# Sheet2.net
KiCad netlist of a schematic drawn in Altium Designer
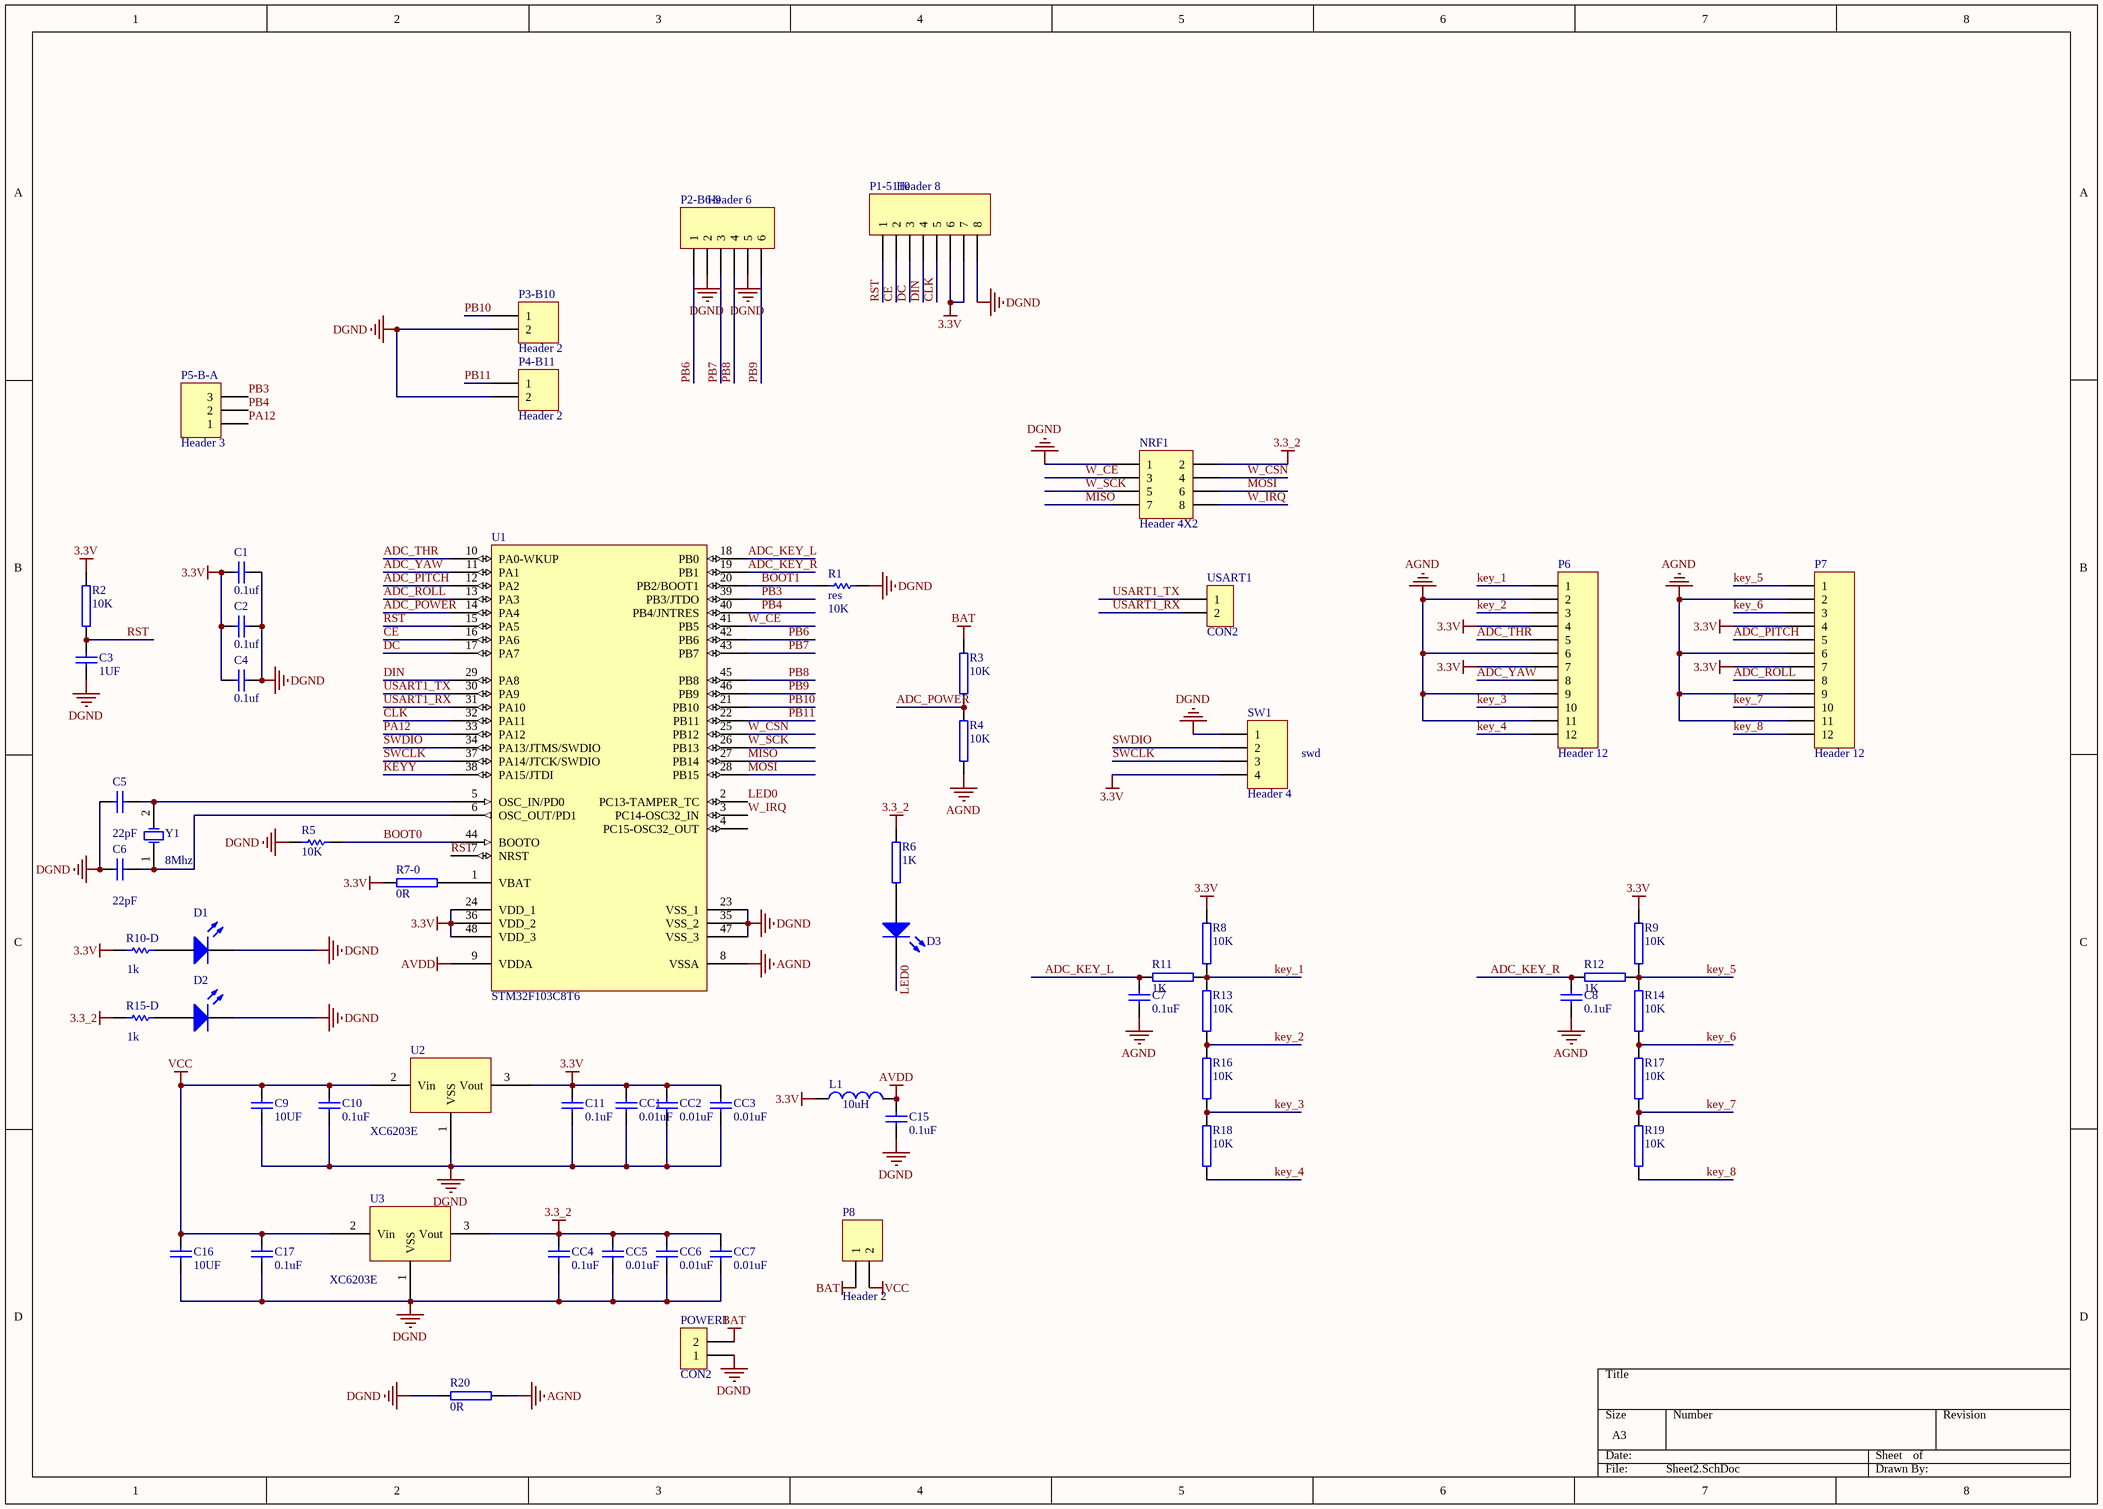
[diagram p0: Sheet2.SchDoc]

(export (version "E")
  (design (tool "Eeschema 10.0.6"))
  (components
    (comp (ref "C1")
      (value "0.1uf")
      (footprint "0603c")
      (fields (field (name "Comment") "cap"))
      (libsource (lib "bai") (part "cap"))
    )
    (comp (ref "C2")
      (value "0.1uf")
      (footprint "0603c")
      (fields (field (name "Comment") "cap"))
      (libsource (lib "bai") (part "cap"))
    )
    (comp (ref "C3")
      (value "1UF")
      (footprint "0603c")
      (fields (field (name "Comment") "cap"))
      (libsource (lib "bai") (part "cap"))
    )
    (comp (ref "C4")
      (value "0.1uf")
      (footprint "0603c")
      (fields (field (name "Comment") "cap"))
      (libsource (lib "bai") (part "cap"))
    )
    (comp (ref "C5")
      (value "22pF")
      (footprint "0603c")
      (fields (field (name "Comment") "cap"))
      (libsource (lib "bai") (part "cap"))
    )
    (comp (ref "C6")
      (value "22pF")
      (footprint "0603c")
      (fields (field (name "Comment") "cap"))
      (libsource (lib "bai") (part "cap"))
    )
    (comp (ref "C7")
      (value "0.1uF")
      (footprint "0603c")
      (fields (field (name "Comment") "cap"))
      (libsource (lib "bai") (part "cap"))
    )
    (comp (ref "C8")
      (value "0.1uF")
      (footprint "0603c")
      (fields (field (name "Comment") "cap"))
      (libsource (lib "bai") (part "cap"))
    )
    (comp (ref "C9")
      (value "10UF")
      (footprint "0805")
      (fields (field (name "Comment") "cap"))
      (libsource (lib "bai") (part "cap"))
    )
    (comp (ref "C10")
      (value "0.1uF")
      (footprint "0603c")
      (fields (field (name "Comment") "cap"))
      (libsource (lib "bai") (part "cap"))
    )
    (comp (ref "C11")
      (value "0.1uF")
      (footprint "0603c")
      (fields (field (name "Comment") "cap"))
      (libsource (lib "bai") (part "cap"))
    )
    (comp (ref "C15")
      (value "0.1uF")
      (footprint "0603c")
      (fields (field (name "Comment") "cap"))
      (libsource (lib "bai") (part "cap"))
    )
    (comp (ref "C16")
      (value "10UF")
      (footprint "0805")
      (fields (field (name "Comment") "cap"))
      (libsource (lib "bai") (part "cap"))
    )
    (comp (ref "C17")
      (value "0.1uF")
      (footprint "0603c")
      (fields (field (name "Comment") "cap"))
      (libsource (lib "bai") (part "cap"))
    )
    (comp (ref "CC1")
      (value "0.01uF")
      (footprint "0603c")
      (fields (field (name "Comment") "cap"))
      (libsource (lib "bai") (part "cap"))
    )
    (comp (ref "CC2")
      (value "0.01uF")
      (footprint "0603c")
      (fields (field (name "Comment") "cap"))
      (libsource (lib "bai") (part "cap"))
    )
    (comp (ref "CC3")
      (value "0.01uF")
      (footprint "0603c")
      (fields (field (name "Comment") "cap"))
      (libsource (lib "bai") (part "cap"))
    )
    (comp (ref "CC4")
      (value "0.1uF")
      (footprint "0603c")
      (fields (field (name "Comment") "cap"))
      (libsource (lib "bai") (part "cap"))
    )
    (comp (ref "CC5")
      (value "0.01uF")
      (footprint "0603c")
      (fields (field (name "Comment") "cap"))
      (libsource (lib "bai") (part "cap"))
    )
    (comp (ref "CC6")
      (value "0.01uF")
      (footprint "0603c")
      (fields (field (name "Comment") "cap"))
      (libsource (lib "bai") (part "cap"))
    )
    (comp (ref "CC7")
      (value "0.01uF")
      (footprint "0603c")
      (fields (field (name "Comment") "cap"))
      (libsource (lib "bai") (part "cap"))
    )
    (comp (ref "D1")
      (value "LED0")
      (footprint "0805")
      (description "Typical INFRARED GaAs LED")
      (fields (field (name "PUBLISHER") "Altium Limited"))
      (libsource (lib "Miscellaneous Devices") (part "LED0"))
    )
    (comp (ref "D2")
      (value "LED0")
      (footprint "0805")
      (description "Typical INFRARED GaAs LED")
      (fields (field (name "PUBLISHER") "Altium Limited"))
      (libsource (lib "Miscellaneous Devices") (part "LED0"))
    )
    (comp (ref "D3")
      (value "LED0")
      (footprint "0805")
      (description "Typical INFRARED GaAs LED")
      (fields (field (name "PUBLISHER") "Altium Limited"))
      (libsource (lib "Miscellaneous Devices") (part "LED0"))
    )
    (comp (ref "L1")
      (value "10uH")
      (footprint "0805")
      (fields (field (name "Comment") "Inductor"))
      (libsource (lib "bai") (part "Inductor"))
    )
    (comp (ref "NRF1")
      (value "Header 4X2")
      (footprint "HDR2X4")
      (description "Header, 4-Pin, Dual row")
      (fields (field (name "PUBLISHER") "Altium Limited"))
      (libsource (lib "Miscellaneous Connectors") (part "Header 4X2"))
    )
    (comp (ref "P1-5110")
      (value "Header 8")
      (footprint "HDR1X8")
      (description "Header, 8-Pin")
      (fields (field (name "PUBLISHER") "Altium Limited"))
      (libsource (lib "Miscellaneous Connectors") (part "Header 8"))
    )
    (comp (ref "P2-B6-9")
      (value "Header 6")
      (footprint "6p")
      (description "Header, 6-Pin")
      (fields (field (name "PUBLISHER") "Altium Limited"))
      (libsource (lib "Miscellaneous Connectors") (part "Header 6"))
    )
    (comp (ref "P3-B10")
      (value "Header 2")
      (footprint "2p")
      (description "Header, 2-Pin")
      (fields (field (name "PUBLISHER") "Altium Limited"))
      (libsource (lib "Miscellaneous Connectors") (part "Header 2"))
    )
    (comp (ref "P4-B11")
      (value "Header 2")
      (footprint "2p")
      (description "Header, 2-Pin")
      (fields (field (name "PUBLISHER") "Altium Limited"))
      (libsource (lib "Miscellaneous Connectors") (part "Header 2"))
    )
    (comp (ref "P5-B-A")
      (value "Header 3")
      (footprint "HDR1X3")
      (description "Header, 3-Pin")
      (fields (field (name "PUBLISHER") "Altium Limited"))
      (libsource (lib "Miscellaneous Connectors") (part "Header 3"))
    )
    (comp (ref "P6")
      (value "Header 12")
      (footprint "12p")
      (description "Header, 12-Pin")
      (fields (field (name "PUBLISHER") "Altium Limited"))
      (libsource (lib "Miscellaneous Connectors") (part "Header 12"))
    )
    (comp (ref "P7")
      (value "Header 12")
      (footprint "12p")
      (description "Header, 12-Pin")
      (fields (field (name "PUBLISHER") "Altium Limited"))
      (libsource (lib "Miscellaneous Connectors") (part "Header 12"))
    )
    (comp (ref "P8")
      (value "Header 2")
      (footprint "2p")
      (description "Header, 2-Pin")
      (fields (field (name "PUBLISHER") "Altium Limited"))
      (libsource (lib "") (part "Header 2_1"))
    )
    (comp (ref "POWER1") (value "CON2") (footprint "2p") (libsource (lib "") (part "CON2_1")))
    (comp (ref "R1")
      (value "res")
      (footprint "0603c")
      (fields (field (name "RES") "10K"))
      (libsource (lib "bai") (part "res"))
    )
    (comp (ref "R2") (value "10K") (footprint "0603c") (libsource (lib "常用元件库") (part "RES")))
    (comp (ref "R3") (value "10K") (footprint "0603c") (libsource (lib "常用元件库") (part "RES")))
    (comp (ref "R4") (value "10K") (footprint "0603c") (libsource (lib "常用元件库") (part "RES")))
    (comp (ref "R5")
      (value "res")
      (footprint "0603c")
      (fields (field (name "RES") "10K"))
      (libsource (lib "bai") (part "res"))
    )
    (comp (ref "R6") (value "1K") (footprint "0603c") (libsource (lib "常用元件库") (part "RES")))
    (comp (ref "R7-0") (value "0R") (footprint "0805") (libsource (lib "常用元件库") (part "RES")))
    (comp (ref "R8") (value "10K") (footprint "0603c") (libsource (lib "常用元件库") (part "RES")))
    (comp (ref "R9") (value "10K") (footprint "0603c") (libsource (lib "常用元件库") (part "RES")))
    (comp (ref "R10-D")
      (value "res")
      (footprint "0603c")
      (fields (field (name "RES") "1k"))
      (libsource (lib "bai") (part "res"))
    )
    (comp (ref "R11") (value "1K") (footprint "0603c") (libsource (lib "常用元件库") (part "RES")))
    (comp (ref "R12") (value "1K") (footprint "0603c") (libsource (lib "常用元件库") (part "RES")))
    (comp (ref "R13") (value "10K") (footprint "0603c") (libsource (lib "常用元件库") (part "RES")))
    (comp (ref "R14") (value "10K") (footprint "0603c") (libsource (lib "常用元件库") (part "RES")))
    (comp (ref "R15-D")
      (value "res")
      (footprint "0603c")
      (fields (field (name "RES") "1k"))
      (libsource (lib "bai") (part "res"))
    )
    (comp (ref "R16") (value "10K") (footprint "0603c") (libsource (lib "常用元件库") (part "RES")))
    (comp (ref "R17") (value "10K") (footprint "0603c") (libsource (lib "常用元件库") (part "RES")))
    (comp (ref "R18") (value "10K") (footprint "0603c") (libsource (lib "常用元件库") (part "RES")))
    (comp (ref "R19") (value "10K") (footprint "0603c") (libsource (lib "常用元件库") (part "RES")))
    (comp (ref "R20") (value "0R") (footprint "0805") (libsource (lib "常用元件库") (part "RES")))
    (comp (ref "SW1")
      (value "Header 4")
      (footprint "HDR1X4")
      (description "Header, 4-Pin")
      (fields (field (name "PUBLISHER") "Altium Limited"))
      (libsource (lib "Miscellaneous Connectors") (part "Header 4"))
    )
    (comp (ref "U1")
      (value "STM32F103C8T6")
      (footprint "LQFP48S")
      (libsource (lib "bai") (part "STM32F103C8T6"))
    )
    (comp (ref "U2") (value "XC6203E") (footprint "SOT-89") (libsource (lib "文哥做的") (part "XC6203")))
    (comp (ref "U3") (value "XC6203E") (footprint "SOT-89") (libsource (lib "文哥做的") (part "XC6203")))
    (comp (ref "USART1") (value "CON2") (footprint "SIP2") (libsource (lib "常用元件库") (part "CON2")))
    (comp (ref "Y1")
      (value "5032xtal")
      (footprint "晶振")
      (fields (field (name "ALTIUM_UNNAMED_1") "8Mhz"))
      (libsource (lib "bai") (part "5032xtal"))
    )
  )
  (nets
    (net (code "1") (name "/ADC_KEY_L") (class "Default")
      (node (ref "C7") (pin "2") (pinfunction "2_2") (pintype "passive"))
      (node (ref "R11") (pin "2") (pinfunction "2_2") (pintype "passive"))
      (node (ref "U1") (pin "18") (pinfunction "PB0_18") (pintype "bidirectional"))
    )
    (net (code "2") (name "/ADC_KEY_R") (class "Default")
      (node (ref "C8") (pin "2") (pinfunction "2_2") (pintype "passive"))
      (node (ref "R12") (pin "2") (pinfunction "2_2") (pintype "passive"))
      (node (ref "U1") (pin "19") (pinfunction "PB1_19") (pintype "bidirectional"))
    )
    (net (code "3") (name "/ADC_PITCH") (class "Default")
      (node (ref "P7") (pin "5") (pinfunction "5_5") (pintype "passive"))
      (node (ref "U1") (pin "12") (pinfunction "PA2_12") (pintype "bidirectional"))
    )
    (net (code "4") (name "/ADC_POWER") (class "Default")
      (node (ref "R3") (pin "1") (pinfunction "1_1") (pintype "passive"))
      (node (ref "R4") (pin "2") (pinfunction "2_2") (pintype "passive"))
      (node (ref "U1") (pin "14") (pinfunction "PA4_14") (pintype "bidirectional"))
    )
    (net (code "5") (name "/ADC_ROLL") (class "Default")
      (node (ref "P7") (pin "8") (pinfunction "8_8") (pintype "passive"))
      (node (ref "U1") (pin "13") (pinfunction "PA3_13") (pintype "bidirectional"))
    )
    (net (code "6") (name "/ADC_THR") (class "Default")
      (node (ref "P6") (pin "5") (pinfunction "5_5") (pintype "passive"))
      (node (ref "U1") (pin "10") (pinfunction "PA0-WKUP_10") (pintype "bidirectional"))
    )
    (net (code "7") (name "/ADC_YAW") (class "Default")
      (node (ref "P6") (pin "8") (pinfunction "8_8") (pintype "passive"))
      (node (ref "U1") (pin "11") (pinfunction "PA1_11") (pintype "bidirectional"))
    )
    (net (code "8") (name "/BOOT0") (class "Default")
      (node (ref "R5") (pin "2") (pinfunction "2_2") (pintype "passive"))
      (node (ref "U1") (pin "44") (pinfunction "BOOTO_44") (pintype "input"))
    )
    (net (code "9") (name "/BOOT1") (class "Default")
      (node (ref "R1") (pin "1") (pinfunction "1_1") (pintype "passive"))
      (node (ref "U1") (pin "20") (pinfunction "PB2/BOOT1_20") (pintype "bidirectional"))
    )
    (net (code "10") (name "/CE") (class "Default")
      (node (ref "P1-5110") (pin "2") (pinfunction "2_2") (pintype "passive"))
      (node (ref "U1") (pin "16") (pinfunction "PA6_16") (pintype "bidirectional"))
    )
    (net (code "11") (name "/CLK") (class "Default")
      (node (ref "P1-5110") (pin "5") (pinfunction "5_5") (pintype "passive"))
      (node (ref "U1") (pin "32") (pinfunction "PA11_32") (pintype "bidirectional"))
    )
    (net (code "12") (name "/DC") (class "Default")
      (node (ref "P1-5110") (pin "3") (pinfunction "3_3") (pintype "passive"))
      (node (ref "U1") (pin "17") (pinfunction "PA7_17") (pintype "bidirectional"))
    )
    (net (code "13") (name "/DIN") (class "Default")
      (node (ref "P1-5110") (pin "4") (pinfunction "4_4") (pintype "passive"))
      (node (ref "U1") (pin "29") (pinfunction "PA8_29") (pintype "bidirectional"))
    )
    (net (code "14") (name "/KEYY") (class "Default")
      (node (ref "U1") (pin "38") (pinfunction "PA15/JTDI_38") (pintype "bidirectional"))
    )
    (net (code "15") (name "/LED0") (class "Default")
      (node (ref "D3") (pin "2") (pinfunction "K_2") (pintype "passive"))
      (node (ref "U1") (pin "2") (pinfunction "PC13-TAMPER_TC_2") (pintype "bidirectional"))
    )
    (net (code "16") (name "/MISO") (class "Default")
      (node (ref "NRF1") (pin "7") (pinfunction "7_7") (pintype "passive"))
      (node (ref "U1") (pin "27") (pinfunction "PB14_27") (pintype "bidirectional"))
    )
    (net (code "17") (name "/MOSI") (class "Default")
      (node (ref "NRF1") (pin "6") (pinfunction "6_6") (pintype "passive"))
      (node (ref "U1") (pin "28") (pinfunction "PB15_28") (pintype "bidirectional"))
    )
    (net (code "18") (name "/PA12") (class "Default")
      (node (ref "P5-B-A") (pin "1") (pinfunction "1_1") (pintype "passive"))
      (node (ref "U1") (pin "33") (pinfunction "PA12_33") (pintype "bidirectional"))
    )
    (net (code "19") (name "/PB3") (class "Default")
      (node (ref "P5-B-A") (pin "3") (pinfunction "3_3") (pintype "passive"))
      (node (ref "U1") (pin "39") (pinfunction "PB3/JTDO_39") (pintype "bidirectional"))
    )
    (net (code "20") (name "/PB4") (class "Default")
      (node (ref "P5-B-A") (pin "2") (pinfunction "2_2") (pintype "passive"))
      (node (ref "U1") (pin "40") (pinfunction "PB4/JNTRES_40") (pintype "bidirectional"))
    )
    (net (code "21") (name "/PB6") (class "Default")
      (node (ref "P2-B6-9") (pin "1") (pinfunction "1_1") (pintype "passive"))
      (node (ref "U1") (pin "42") (pinfunction "PB6_42") (pintype "bidirectional"))
    )
    (net (code "22") (name "/PB7") (class "Default")
      (node (ref "P2-B6-9") (pin "3") (pinfunction "3_3") (pintype "passive"))
      (node (ref "U1") (pin "43") (pinfunction "PB7_43") (pintype "bidirectional"))
    )
    (net (code "23") (name "/PB8") (class "Default")
      (node (ref "P2-B6-9") (pin "4") (pinfunction "4_4") (pintype "passive"))
      (node (ref "U1") (pin "45") (pinfunction "PB8_45") (pintype "bidirectional"))
    )
    (net (code "24") (name "/PB9") (class "Default")
      (node (ref "P2-B6-9") (pin "6") (pinfunction "6_6") (pintype "passive"))
      (node (ref "U1") (pin "46") (pinfunction "PB9_46") (pintype "bidirectional"))
    )
    (net (code "25") (name "/PB10") (class "Default")
      (node (ref "P3-B10") (pin "1") (pinfunction "1_1") (pintype "passive"))
      (node (ref "U1") (pin "21") (pinfunction "PB10_21") (pintype "bidirectional"))
    )
    (net (code "26") (name "/PB11") (class "Default")
      (node (ref "P4-B11") (pin "1") (pinfunction "1_1") (pintype "passive"))
      (node (ref "U1") (pin "22") (pinfunction "PB11_22") (pintype "bidirectional"))
    )
    (net (code "27") (name "/RST") (class "Default")
      (node (ref "C3") (pin "2") (pinfunction "2_2") (pintype "passive"))
      (node (ref "P1-5110") (pin "1") (pinfunction "1_1") (pintype "passive"))
      (node (ref "R2") (pin "1") (pinfunction "1_1") (pintype "passive"))
      (node (ref "U1") (pin "15") (pinfunction "PA5_15") (pintype "bidirectional"))
      (node (ref "U1") (pin "7") (pinfunction "NRST_7") (pintype "bidirectional"))
    )
    (net (code "28") (name "/SWCLK") (class "Default")
      (node (ref "SW1") (pin "3") (pinfunction "3_3") (pintype "passive"))
      (node (ref "U1") (pin "37") (pinfunction "PA14/JTCK/SWDIO_37") (pintype "bidirectional"))
    )
    (net (code "29") (name "/SWDIO") (class "Default")
      (node (ref "SW1") (pin "2") (pinfunction "2_2") (pintype "passive"))
      (node (ref "U1") (pin "34") (pinfunction "PA13/JTMS/SWDIO_34") (pintype "bidirectional"))
    )
    (net (code "30") (name "/USART1_RX") (class "Default")
      (node (ref "U1") (pin "31") (pinfunction "PA10_31") (pintype "bidirectional"))
      (node (ref "USART1") (pin "2") (pinfunction "2_2") (pintype "passive"))
    )
    (net (code "31") (name "/USART1_TX") (class "Default")
      (node (ref "U1") (pin "30") (pinfunction "PA9_30") (pintype "bidirectional"))
      (node (ref "USART1") (pin "1") (pinfunction "1_1") (pintype "passive"))
    )
    (net (code "32") (name "/W_CE") (class "Default")
      (node (ref "NRF1") (pin "3") (pinfunction "3_3") (pintype "passive"))
      (node (ref "U1") (pin "41") (pinfunction "PB5_41") (pintype "bidirectional"))
    )
    (net (code "33") (name "/W_CSN") (class "Default")
      (node (ref "NRF1") (pin "4") (pinfunction "4_4") (pintype "passive"))
      (node (ref "U1") (pin "25") (pinfunction "PB12_25") (pintype "bidirectional"))
    )
    (net (code "34") (name "/W_IRQ") (class "Default")
      (node (ref "NRF1") (pin "8") (pinfunction "8_8") (pintype "passive"))
      (node (ref "U1") (pin "3") (pinfunction "PC14-OSC32_IN_3") (pintype "bidirectional"))
    )
    (net (code "35") (name "/W_SCK") (class "Default")
      (node (ref "NRF1") (pin "5") (pinfunction "5_5") (pintype "passive"))
      (node (ref "U1") (pin "26") (pinfunction "PB13_26") (pintype "bidirectional"))
    )
    (net (code "36") (name "/key_1") (class "Default")
      (node (ref "P6") (pin "1") (pinfunction "1_1") (pintype "passive"))
      (node (ref "R11") (pin "1") (pinfunction "1_1") (pintype "passive"))
      (node (ref "R13") (pin "2") (pinfunction "2_2") (pintype "passive"))
      (node (ref "R8") (pin "1") (pinfunction "1_1") (pintype "passive"))
    )
    (net (code "37") (name "/key_2") (class "Default")
      (node (ref "P6") (pin "3") (pinfunction "3_3") (pintype "passive"))
      (node (ref "R13") (pin "1") (pinfunction "1_1") (pintype "passive"))
      (node (ref "R16") (pin "2") (pinfunction "2_2") (pintype "passive"))
    )
    (net (code "38") (name "/key_3") (class "Default")
      (node (ref "P6") (pin "10") (pinfunction "10_10") (pintype "passive"))
      (node (ref "R16") (pin "1") (pinfunction "1_1") (pintype "passive"))
      (node (ref "R18") (pin "2") (pinfunction "2_2") (pintype "passive"))
    )
    (net (code "39") (name "/key_4") (class "Default")
      (node (ref "P6") (pin "12") (pinfunction "12_12") (pintype "passive"))
      (node (ref "R18") (pin "1") (pinfunction "1_1") (pintype "passive"))
    )
    (net (code "40") (name "/key_5") (class "Default")
      (node (ref "P7") (pin "1") (pinfunction "1_1") (pintype "passive"))
      (node (ref "R12") (pin "1") (pinfunction "1_1") (pintype "passive"))
      (node (ref "R14") (pin "2") (pinfunction "2_2") (pintype "passive"))
      (node (ref "R9") (pin "1") (pinfunction "1_1") (pintype "passive"))
    )
    (net (code "41") (name "/key_6") (class "Default")
      (node (ref "P7") (pin "3") (pinfunction "3_3") (pintype "passive"))
      (node (ref "R14") (pin "1") (pinfunction "1_1") (pintype "passive"))
      (node (ref "R17") (pin "2") (pinfunction "2_2") (pintype "passive"))
    )
    (net (code "42") (name "/key_7") (class "Default")
      (node (ref "P7") (pin "10") (pinfunction "10_10") (pintype "passive"))
      (node (ref "R17") (pin "1") (pinfunction "1_1") (pintype "passive"))
      (node (ref "R19") (pin "2") (pinfunction "2_2") (pintype "passive"))
    )
    (net (code "43") (name "/key_8") (class "Default")
      (node (ref "P7") (pin "12") (pinfunction "12_12") (pintype "passive"))
      (node (ref "R19") (pin "1") (pinfunction "1_1") (pintype "passive"))
    )
    (net (code "44") (name "3.3V") (class "Default")
      (node (ref "C1") (pin "2") (pinfunction "2_2") (pintype "passive"))
      (node (ref "C11") (pin "2") (pinfunction "2_2") (pintype "passive"))
      (node (ref "C2") (pin "2") (pinfunction "2_2") (pintype "passive"))
      (node (ref "C4") (pin "2") (pinfunction "2_2") (pintype "passive"))
      (node (ref "CC1") (pin "2") (pinfunction "2_2") (pintype "passive"))
      (node (ref "CC2") (pin "2") (pinfunction "2_2") (pintype "passive"))
      (node (ref "CC3") (pin "2") (pinfunction "2_2") (pintype "passive"))
      (node (ref "L1") (pin "1") (pinfunction "1_1") (pintype "passive"))
      (node (ref "P1-5110") (pin "6") (pinfunction "6_6") (pintype "passive"))
      (node (ref "P1-5110") (pin "7") (pinfunction "7_7") (pintype "passive"))
      (node (ref "P6") (pin "4") (pinfunction "4_4") (pintype "passive"))
      (node (ref "P6") (pin "7") (pinfunction "7_7") (pintype "passive"))
      (node (ref "P7") (pin "4") (pinfunction "4_4") (pintype "passive"))
      (node (ref "P7") (pin "7") (pinfunction "7_7") (pintype "passive"))
      (node (ref "R10-D") (pin "1") (pinfunction "1_1") (pintype "passive"))
      (node (ref "R2") (pin "2") (pinfunction "2_2") (pintype "passive"))
      (node (ref "R7-0") (pin "2") (pinfunction "2_2") (pintype "passive"))
      (node (ref "R8") (pin "2") (pinfunction "2_2") (pintype "passive"))
      (node (ref "R9") (pin "2") (pinfunction "2_2") (pintype "passive"))
      (node (ref "SW1") (pin "4") (pinfunction "4_4") (pintype "passive"))
      (node (ref "U1") (pin "24") (pinfunction "VDD_1_24") (pintype "passive"))
      (node (ref "U1") (pin "36") (pinfunction "VDD_2_36") (pintype "passive"))
      (node (ref "U1") (pin "48") (pinfunction "VDD_3_48") (pintype "passive"))
      (node (ref "U2") (pin "3") (pinfunction "Vout_3") (pintype "passive"))
    )
    (net (code "45") (name "3.3_2") (class "Default")
      (node (ref "CC4") (pin "2") (pinfunction "2_2") (pintype "passive"))
      (node (ref "CC5") (pin "2") (pinfunction "2_2") (pintype "passive"))
      (node (ref "CC6") (pin "2") (pinfunction "2_2") (pintype "passive"))
      (node (ref "CC7") (pin "2") (pinfunction "2_2") (pintype "passive"))
      (node (ref "NRF1") (pin "2") (pinfunction "2_2") (pintype "passive"))
      (node (ref "R15-D") (pin "1") (pinfunction "1_1") (pintype "passive"))
      (node (ref "R6") (pin "2") (pinfunction "2_2") (pintype "passive"))
      (node (ref "U3") (pin "3") (pinfunction "Vout_3") (pintype "passive"))
    )
    (net (code "46") (name "AGND") (class "Default")
      (node (ref "C7") (pin "1") (pinfunction "1_1") (pintype "passive"))
      (node (ref "C8") (pin "1") (pinfunction "1_1") (pintype "passive"))
      (node (ref "P6") (pin "11") (pinfunction "11_11") (pintype "passive"))
      (node (ref "P6") (pin "2") (pinfunction "2_2") (pintype "passive"))
      (node (ref "P6") (pin "6") (pinfunction "6_6") (pintype "passive"))
      (node (ref "P6") (pin "9") (pinfunction "9_9") (pintype "passive"))
      (node (ref "P7") (pin "11") (pinfunction "11_11") (pintype "passive"))
      (node (ref "P7") (pin "2") (pinfunction "2_2") (pintype "passive"))
      (node (ref "P7") (pin "6") (pinfunction "6_6") (pintype "passive"))
      (node (ref "P7") (pin "9") (pinfunction "9_9") (pintype "passive"))
      (node (ref "R20") (pin "2") (pinfunction "2_2") (pintype "passive"))
      (node (ref "R4") (pin "1") (pinfunction "1_1") (pintype "passive"))
      (node (ref "U1") (pin "8") (pinfunction "VSSA_8") (pintype "passive"))
    )
    (net (code "47") (name "AVDD") (class "Default")
      (node (ref "C15") (pin "2") (pinfunction "2_2") (pintype "passive"))
      (node (ref "L1") (pin "2") (pinfunction "2_2") (pintype "passive"))
      (node (ref "U1") (pin "9") (pinfunction "VDDA_9") (pintype "passive"))
    )
    (net (code "48") (name "BAT") (class "Default")
      (node (ref "P8") (pin "1") (pinfunction "1_1") (pintype "passive"))
      (node (ref "POWER1") (pin "2") (pinfunction "2_2") (pintype "passive"))
      (node (ref "R3") (pin "2") (pinfunction "2_2") (pintype "passive"))
    )
    (net (code "49") (name "DGND") (class "Default")
      (node (ref "C1") (pin "1") (pinfunction "1_1") (pintype "passive"))
      (node (ref "C10") (pin "1") (pinfunction "1_1") (pintype "passive"))
      (node (ref "C11") (pin "1") (pinfunction "1_1") (pintype "passive"))
      (node (ref "C15") (pin "1") (pinfunction "1_1") (pintype "passive"))
      (node (ref "C16") (pin "1") (pinfunction "1_1") (pintype "passive"))
      (node (ref "C17") (pin "1") (pinfunction "1_1") (pintype "passive"))
      (node (ref "C2") (pin "1") (pinfunction "1_1") (pintype "passive"))
      (node (ref "C3") (pin "1") (pinfunction "1_1") (pintype "passive"))
      (node (ref "C4") (pin "1") (pinfunction "1_1") (pintype "passive"))
      (node (ref "C5") (pin "1") (pinfunction "1_1") (pintype "passive"))
      (node (ref "C6") (pin "1") (pinfunction "1_1") (pintype "passive"))
      (node (ref "C9") (pin "1") (pinfunction "1_1") (pintype "passive"))
      (node (ref "CC1") (pin "1") (pinfunction "1_1") (pintype "passive"))
      (node (ref "CC2") (pin "1") (pinfunction "1_1") (pintype "passive"))
      (node (ref "CC3") (pin "1") (pinfunction "1_1") (pintype "passive"))
      (node (ref "CC4") (pin "1") (pinfunction "1_1") (pintype "passive"))
      (node (ref "CC5") (pin "1") (pinfunction "1_1") (pintype "passive"))
      (node (ref "CC6") (pin "1") (pinfunction "1_1") (pintype "passive"))
      (node (ref "CC7") (pin "1") (pinfunction "1_1") (pintype "passive"))
      (node (ref "D1") (pin "2") (pinfunction "K_2") (pintype "passive"))
      (node (ref "D2") (pin "2") (pinfunction "K_2") (pintype "passive"))
      (node (ref "NRF1") (pin "1") (pinfunction "1_1") (pintype "passive"))
      (node (ref "P1-5110") (pin "8") (pinfunction "8_8") (pintype "passive"))
      (node (ref "P2-B6-9") (pin "2") (pinfunction "2_2") (pintype "passive"))
      (node (ref "P2-B6-9") (pin "5") (pinfunction "5_5") (pintype "passive"))
      (node (ref "P3-B10") (pin "2") (pinfunction "2_2") (pintype "passive"))
      (node (ref "P4-B11") (pin "2") (pinfunction "2_2") (pintype "passive"))
      (node (ref "POWER1") (pin "1") (pinfunction "1_1") (pintype "passive"))
      (node (ref "R1") (pin "2") (pinfunction "2_2") (pintype "passive"))
      (node (ref "R20") (pin "1") (pinfunction "1_1") (pintype "passive"))
      (node (ref "R5") (pin "1") (pinfunction "1_1") (pintype "passive"))
      (node (ref "SW1") (pin "1") (pinfunction "1_1") (pintype "passive"))
      (node (ref "U1") (pin "23") (pinfunction "VSS_1_23") (pintype "passive"))
      (node (ref "U1") (pin "35") (pinfunction "VSS_2_35") (pintype "passive"))
      (node (ref "U1") (pin "47") (pinfunction "VSS_3_47") (pintype "passive"))
      (node (ref "U2") (pin "1") (pinfunction "VSS_1") (pintype "passive"))
      (node (ref "U3") (pin "1") (pinfunction "VSS_1") (pintype "passive"))
    )
    (net (code "50") (name "Net-(D1-A)") (class "Default")
      (node (ref "D1") (pin "1") (pinfunction "A_1") (pintype "passive"))
      (node (ref "R10-D") (pin "2") (pinfunction "2_2") (pintype "passive"))
    )
    (net (code "51") (name "Net-(D2-A)") (class "Default")
      (node (ref "D2") (pin "1") (pinfunction "A_1") (pintype "passive"))
      (node (ref "R15-D") (pin "2") (pinfunction "2_2") (pintype "passive"))
    )
    (net (code "52") (name "Net-(D3-A)") (class "Default")
      (node (ref "D3") (pin "1") (pinfunction "A_1") (pintype "passive"))
      (node (ref "R6") (pin "1") (pinfunction "1_1") (pintype "passive"))
    )
    (net (code "53") (name "Net-(U1-OSC_IN{slash}PD0)") (class "Default")
      (node (ref "C5") (pin "2") (pinfunction "2_2") (pintype "passive"))
      (node (ref "U1") (pin "5") (pinfunction "OSC_IN/PD0_5") (pintype "input"))
      (node (ref "Y1") (pin "2") (pinfunction "OSC2_2") (pintype "passive"))
    )
    (net (code "54") (name "Net-(U1-OSC_OUT{slash}PD1)") (class "Default")
      (node (ref "C6") (pin "2") (pinfunction "2_2") (pintype "passive"))
      (node (ref "U1") (pin "6") (pinfunction "OSC_OUT/PD1_6") (pintype "output"))
      (node (ref "Y1") (pin "1") (pinfunction "OSC1_1") (pintype "passive"))
    )
    (net (code "55") (name "Net-(U1-VBAT)") (class "Default")
      (node (ref "R7-0") (pin "1") (pinfunction "1_1") (pintype "passive"))
      (node (ref "U1") (pin "1") (pinfunction "VBAT_1") (pintype "passive"))
    )
    (net (code "56") (name "VCC") (class "Default")
      (node (ref "C10") (pin "2") (pinfunction "2_2") (pintype "passive"))
      (node (ref "C16") (pin "2") (pinfunction "2_2") (pintype "passive"))
      (node (ref "C17") (pin "2") (pinfunction "2_2") (pintype "passive"))
      (node (ref "C9") (pin "2") (pinfunction "2_2") (pintype "passive"))
      (node (ref "P8") (pin "2") (pinfunction "2_2") (pintype "passive"))
      (node (ref "U2") (pin "2") (pinfunction "Vin_2") (pintype "passive"))
      (node (ref "U3") (pin "2") (pinfunction "Vin_2") (pintype "passive"))
    )
    (net (code "57") (name "unconnected-(U1-PC15-OSC32_OUT-Pad4)") (class "Default")
      (node (ref "U1") (pin "4") (pinfunction "PC15-OSC32_OUT_4") (pintype "bidirectional"))
    )
  )
)
